# module.net
KiCad netlist of a schematic drawn in EAGLE
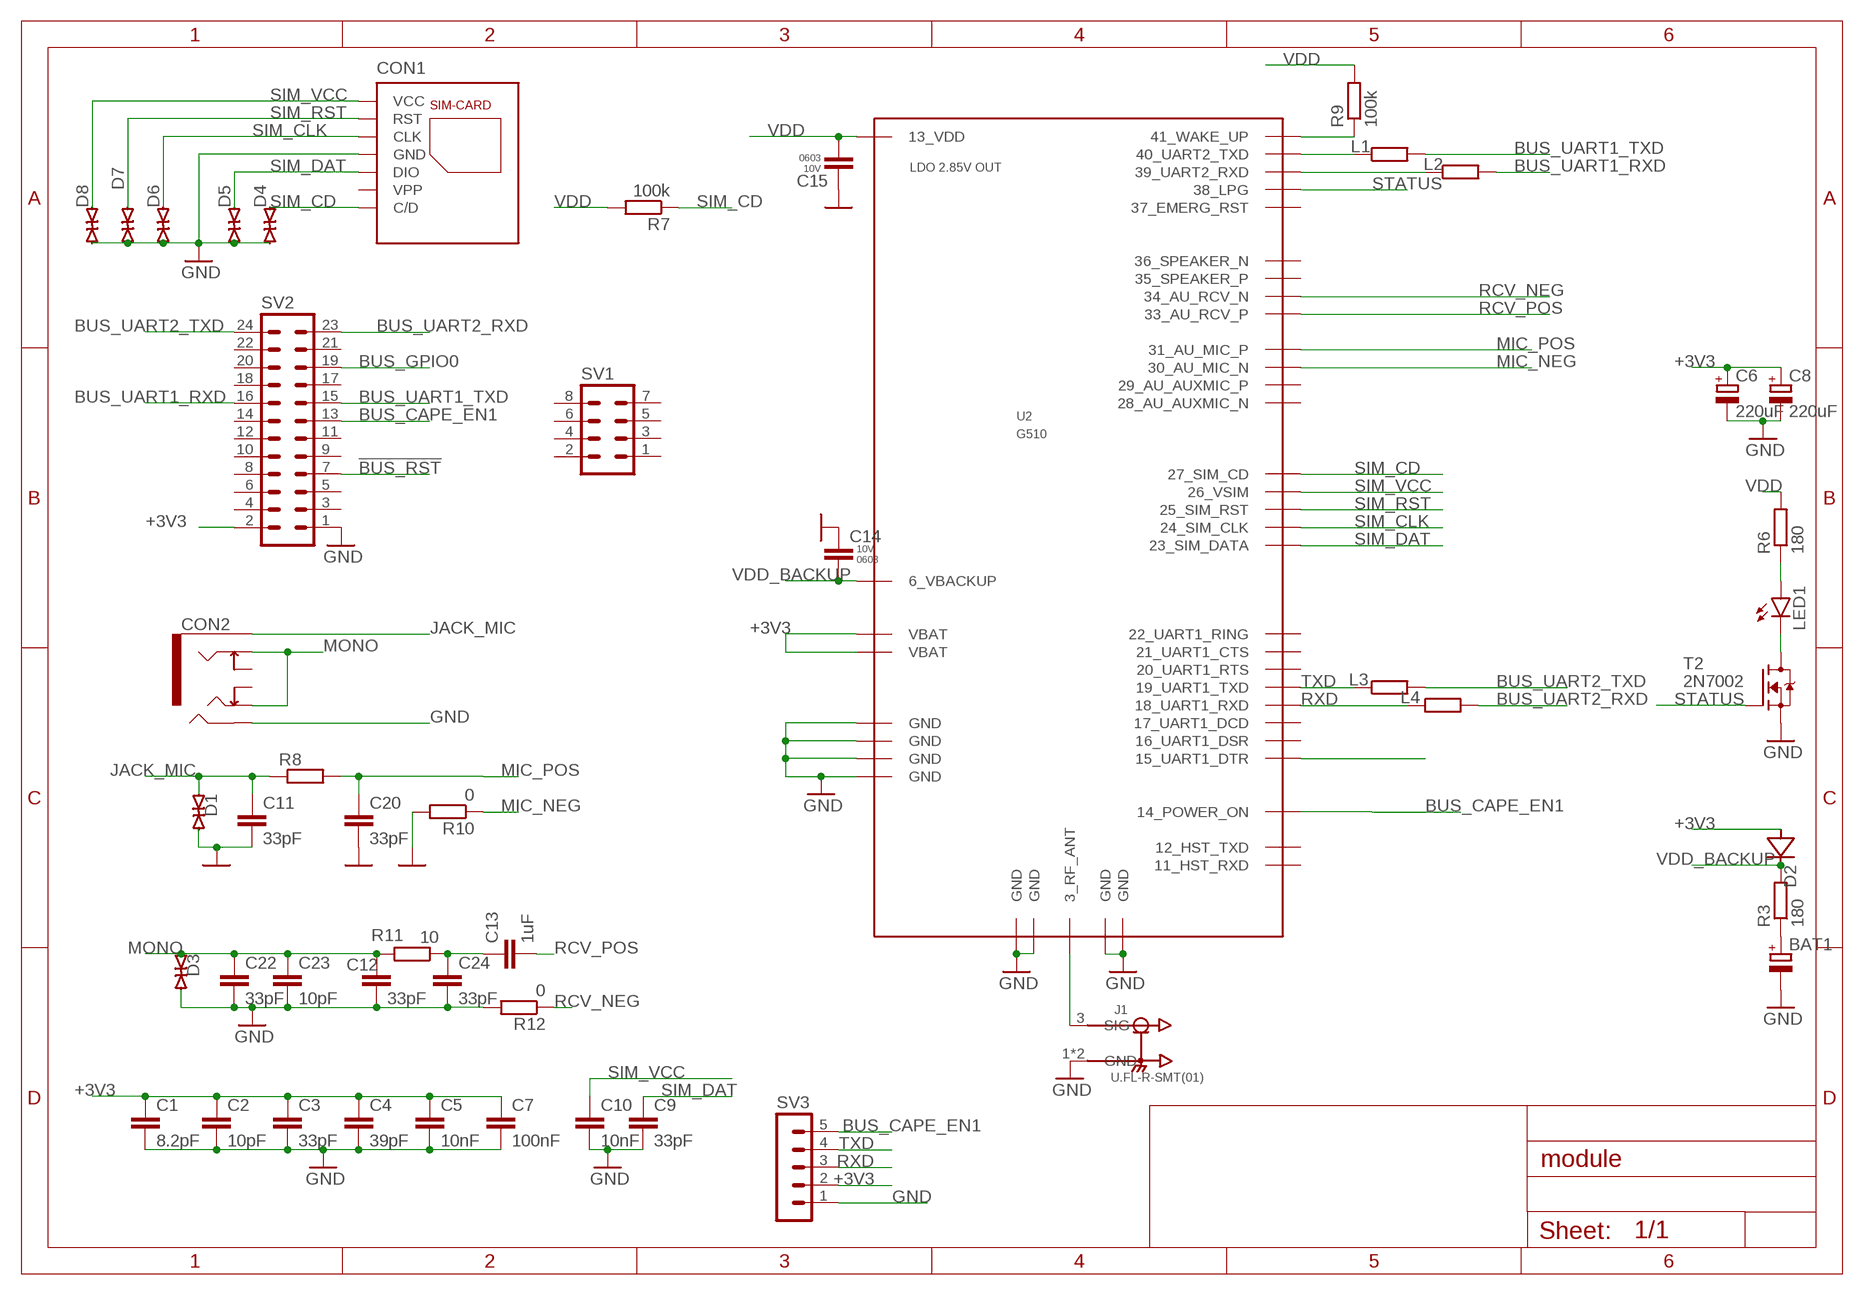
[diagram p0: schematic, sheet 1]

(export (version "E")
  (design (tool "Eeschema 10.0.6"))
  (components
    (comp (ref "BAT1")
      (value "DCK-3R3E224U-E")
      (footprint "eagle-import:621")
      (libsource (lib "eagle-import") (part "DCK-3R3E224U-E"))
    )
    (comp (ref "C1")
      (value "8.2pF")
      (footprint "eagle-import:C0402K")
      (libsource (lib "eagle-import") (part "CAP-0402"))
    )
    (comp (ref "C2")
      (value "10pF")
      (footprint "eagle-import:C0402K")
      (libsource (lib "eagle-import") (part "CAP-0402"))
    )
    (comp (ref "C3")
      (value "33pF")
      (footprint "eagle-import:C0402K")
      (libsource (lib "eagle-import") (part "CAP-0402"))
    )
    (comp (ref "C4")
      (value "39pF")
      (footprint "eagle-import:C0402K")
      (libsource (lib "eagle-import") (part "CAP-0402"))
    )
    (comp (ref "C5")
      (value "10nF")
      (footprint "eagle-import:C0603")
      (libsource (lib "eagle-import") (part "C-EUC0603"))
    )
    (comp (ref "C6")
      (value "220uF")
      (footprint "eagle-import:SMC_C")
      (libsource (lib "eagle-import") (part "CAP-POL-SMC"))
    )
    (comp (ref "C7")
      (value "100nF")
      (footprint "eagle-import:C0603")
      (libsource (lib "eagle-import") (part "C-EUC0603"))
    )
    (comp (ref "C8")
      (value "220uF")
      (footprint "eagle-import:SMC_C")
      (libsource (lib "eagle-import") (part "CAP-POL-SMC"))
    )
    (comp (ref "C9")
      (value "33pF")
      (footprint "eagle-import:C0603")
      (libsource (lib "eagle-import") (part "CAP-0603"))
    )
    (comp (ref "C10")
      (value "10nF")
      (footprint "eagle-import:C0603")
      (libsource (lib "eagle-import") (part "CAP-0603"))
    )
    (comp (ref "C11")
      (value "33pF")
      (footprint "eagle-import:C0402K")
      (libsource (lib "eagle-import") (part "CAP-0402"))
    )
    (comp (ref "C12")
      (value "33pF")
      (footprint "eagle-import:C0402K")
      (libsource (lib "eagle-import") (part "CAP-0402"))
    )
    (comp (ref "C13")
      (value "1uF")
      (footprint "eagle-import:C0402K")
      (libsource (lib "eagle-import") (part "CAP-0402"))
    )
    (comp (ref "C14")
      (value "CAP-0603")
      (footprint "eagle-import:C0603")
      (fields (field (name "RATING") "10V") (field (name "PACKAGE") "0603"))
      (libsource (lib "eagle-import") (part "CAP-0603"))
    )
    (comp (ref "C15")
      (value "CAP-0603")
      (footprint "eagle-import:C0603")
      (fields (field (name "RATING") "10V") (field (name "PACKAGE") "0603"))
      (libsource (lib "eagle-import") (part "CAP-0603"))
    )
    (comp (ref "C20")
      (value "33pF")
      (footprint "eagle-import:C0402K")
      (libsource (lib "eagle-import") (part "CAP-0402"))
    )
    (comp (ref "C22")
      (value "33pF")
      (footprint "eagle-import:C0402K")
      (libsource (lib "eagle-import") (part "CAP-0402"))
    )
    (comp (ref "C23")
      (value "10pF")
      (footprint "eagle-import:C0402K")
      (libsource (lib "eagle-import") (part "CAP-0402"))
    )
    (comp (ref "C24")
      (value "33pF")
      (footprint "eagle-import:C0402K")
      (libsource (lib "eagle-import") (part "CAP-0402"))
    )
    (comp (ref "CON1")
      (value "115Q-BCA0")
      (footprint "eagle-import:115Q")
      (libsource (lib "eagle-import") (part "115Q-BCA0"))
    )
    (comp (ref "CON2")
      (value "1503-21")
      (footprint "eagle-import:150321")
      (libsource (lib "eagle-import") (part "1503-21"))
    )
    (comp (ref "D1")
      (value "ESD9B5.0ST5G")
      (footprint "eagle-import:SOD1006X40")
      (libsource (lib "eagle-import") (part "ESD9B5.0ST5G"))
    )
    (comp (ref "D2")
      (value "1N4148WS")
      (footprint "eagle-import:SOD323")
      (libsource (lib "eagle-import") (part "1N4148WS"))
    )
    (comp (ref "D3")
      (value "ESD9B5.0ST5G")
      (footprint "eagle-import:SOD1006X40")
      (libsource (lib "eagle-import") (part "ESD9B5.0ST5G"))
    )
    (comp (ref "D4")
      (value "ESD9B5.0ST5G")
      (footprint "eagle-import:SOD1006X40")
      (libsource (lib "eagle-import") (part "ESD9B5.0ST5G"))
    )
    (comp (ref "D5")
      (value "ESD9B5.0ST5G")
      (footprint "eagle-import:SOD1006X40")
      (libsource (lib "eagle-import") (part "ESD9B5.0ST5G"))
    )
    (comp (ref "D6")
      (value "ESD9B5.0ST5G")
      (footprint "eagle-import:SOD1006X40")
      (libsource (lib "eagle-import") (part "ESD9B5.0ST5G"))
    )
    (comp (ref "D7")
      (value "ESD9B5.0ST5G")
      (footprint "eagle-import:SOD1006X40")
      (libsource (lib "eagle-import") (part "ESD9B5.0ST5G"))
    )
    (comp (ref "D8")
      (value "ESD9B5.0ST5G")
      (footprint "eagle-import:SOD1006X40")
      (libsource (lib "eagle-import") (part "ESD9B5.0ST5G"))
    )
    (comp (ref "J1")
      (value "U.FL-R-SMT(01)")
      (footprint "eagle-import:HRS_U.FL-R-SMT(01)")
      (fields (field (name "MF") "Hirose") (field (name "MP") "U.FL-R-SMT_01_"))
      (libsource (lib "eagle-import") (part "U.FL-R-SMT(01)"))
    )
    (comp (ref "L1")
      (value "RES-0603")
      (footprint "eagle-import:R0603")
      (libsource (lib "eagle-import") (part "RES-0603"))
    )
    (comp (ref "L2")
      (value "RES-0603")
      (footprint "eagle-import:R0603")
      (libsource (lib "eagle-import") (part "RES-0603"))
    )
    (comp (ref "L3")
      (value "RES-0603")
      (footprint "eagle-import:R0603")
      (libsource (lib "eagle-import") (part "RES-0603"))
    )
    (comp (ref "L4")
      (value "RES-0603")
      (footprint "eagle-import:R0603")
      (libsource (lib "eagle-import") (part "RES-0603"))
    )
    (comp (ref "LED1")
      (value "LEDCHIP-LED0603")
      (footprint "eagle-import:CHIP-LED0603")
      (libsource (lib "eagle-import") (part "LEDCHIP-LED0603"))
    )
    (comp (ref "R3")
      (value "180")
      (footprint "eagle-import:R0603")
      (libsource (lib "eagle-import") (part "RES-0603"))
    )
    (comp (ref "R6")
      (value "180")
      (footprint "eagle-import:R0603")
      (libsource (lib "eagle-import") (part "RES-0603"))
    )
    (comp (ref "R7")
      (value "100k")
      (footprint "eagle-import:R0603")
      (libsource (lib "eagle-import") (part "RES-0603"))
    )
    (comp (ref "R8")
      (value "R-EU_R0402")
      (footprint "eagle-import:R0402")
      (libsource (lib "eagle-import") (part "R-EU_R0402"))
    )
    (comp (ref "R9")
      (value "100k")
      (footprint "eagle-import:R0603")
      (libsource (lib "eagle-import") (part "RES-0603"))
    )
    (comp (ref "R10")
      (value "0")
      (footprint "eagle-import:R0402")
      (libsource (lib "eagle-import") (part "R-EU_R0402"))
    )
    (comp (ref "R11")
      (value "10")
      (footprint "eagle-import:R0402")
      (libsource (lib "eagle-import") (part "R-EU_R0402"))
    )
    (comp (ref "R12")
      (value "0")
      (footprint "eagle-import:R0402")
      (libsource (lib "eagle-import") (part "R-EU_R0402"))
    )
    (comp (ref "SV1")
      (value "MA04-2")
      (footprint "eagle-import:MA04-2")
      (libsource (lib "eagle-import") (part "MA04-2"))
    )
    (comp (ref "SV2")
      (value "MA12-2")
      (footprint "eagle-import:MA12-2")
      (libsource (lib "eagle-import") (part "MA12-2"))
    )
    (comp (ref "SV3")
      (value "MA05-1")
      (footprint "eagle-import:MA05-1")
      (libsource (lib "eagle-import") (part "MA05-1"))
    )
    (comp (ref "T2")
      (value "2N7002")
      (footprint "eagle-import:SOT95P240X110-3")
      (libsource (lib "eagle-import") (part "2N7002"))
    )
    (comp (ref "U2")
      (value "G510")
      (footprint "eagle-import:G510")
      (libsource (lib "eagle-import") (part "G510"))
    )
  )
  (nets
    (net (code "1") (name "/+3V3") (class "Default")
      (node (ref "C1") (pin "1") (pinfunction "1_1") (pintype "passive"))
      (node (ref "C2") (pin "1") (pinfunction "1_1") (pintype "passive"))
      (node (ref "C3") (pin "1") (pinfunction "1_1") (pintype "passive"))
      (node (ref "C4") (pin "1") (pinfunction "1_1") (pintype "passive"))
      (node (ref "C5") (pin "1") (pinfunction "1_1") (pintype "passive"))
      (node (ref "C6") (pin "+") (pinfunction "+_+") (pintype "passive"))
      (node (ref "C7") (pin "1") (pinfunction "1_1") (pintype "passive"))
      (node (ref "C8") (pin "+") (pinfunction "+_+") (pintype "passive"))
      (node (ref "D2") (pin "A") (pinfunction "A_A") (pintype "passive"))
      (node (ref "SV2") (pin "2") (pinfunction "2_2") (pintype "passive"))
      (node (ref "SV3") (pin "2") (pinfunction "2_2") (pintype "passive"))
      (node (ref "U2") (pin "10_VBAT") (pinfunction "VBAT_10_VBAT") (pintype "power_in"))
      (node (ref "U2") (pin "9_VBAT") (pinfunction "VBAT_9_VBAT") (pintype "power_in"))
    )
    (net (code "2") (name "/BUS_CAPE_EN1") (class "Default")
      (node (ref "SV2") (pin "13") (pinfunction "13_13") (pintype "passive"))
      (node (ref "SV3") (pin "5") (pinfunction "5_5") (pintype "passive"))
      (node (ref "U2") (pin "14_POWER_ON") (pinfunction "14_POWER_ON_14_POWER_ON") (pintype "input"))
    )
    (net (code "3") (name "/BUS_GPIO0") (class "Default")
      (node (ref "SV2") (pin "19") (pinfunction "19_19") (pintype "passive"))
    )
    (net (code "4") (name "/BUS_UART1_RXD") (class "Default")
      (node (ref "L2") (pin "2") (pinfunction "2_2") (pintype "passive"))
      (node (ref "SV2") (pin "16") (pinfunction "16_16") (pintype "passive"))
    )
    (net (code "5") (name "/BUS_UART1_TXD") (class "Default")
      (node (ref "L1") (pin "2") (pinfunction "2_2") (pintype "passive"))
      (node (ref "SV2") (pin "15") (pinfunction "15_15") (pintype "passive"))
    )
    (net (code "6") (name "/BUS_UART2_RXD") (class "Default")
      (node (ref "L4") (pin "2") (pinfunction "2_2") (pintype "passive"))
      (node (ref "SV2") (pin "23") (pinfunction "23_23") (pintype "passive"))
    )
    (net (code "7") (name "/BUS_UART2_TXD") (class "Default")
      (node (ref "L3") (pin "2") (pinfunction "2_2") (pintype "passive"))
      (node (ref "SV2") (pin "24") (pinfunction "24_24") (pintype "passive"))
    )
    (net (code "8") (name "/JACK_MIC") (class "Default")
      (node (ref "C11") (pin "1") (pinfunction "1_1") (pintype "passive"))
      (node (ref "CON2") (pin "1") (pinfunction "1_1") (pintype "bidirectional"))
      (node (ref "D1") (pin "1") (pinfunction "A_1") (pintype "passive"))
      (node (ref "R8") (pin "1") (pinfunction "1_1") (pintype "passive"))
    )
    (net (code "9") (name "/MIC_NEG") (class "Default")
      (node (ref "R10") (pin "1") (pinfunction "1_1") (pintype "passive"))
      (node (ref "U2") (pin "30_AU_MIC_N") (pinfunction "30_AU_MIC_N_30_AU_MIC_N") (pintype "bidirectional"))
    )
    (net (code "10") (name "/MIC_POS") (class "Default")
      (node (ref "C20") (pin "1") (pinfunction "1_1") (pintype "passive"))
      (node (ref "R8") (pin "2") (pinfunction "2_2") (pintype "passive"))
      (node (ref "U2") (pin "31_AU_MIC_P") (pinfunction "31_AU_MIC_P_31_AU_MIC_P") (pintype "bidirectional"))
    )
    (net (code "11") (name "/MONO") (class "Default")
      (node (ref "C12") (pin "1") (pinfunction "1_1") (pintype "passive"))
      (node (ref "C22") (pin "1") (pinfunction "1_1") (pintype "passive"))
      (node (ref "C23") (pin "1") (pinfunction "1_1") (pintype "passive"))
      (node (ref "CON2") (pin "3") (pinfunction "3_3") (pintype "bidirectional"))
      (node (ref "CON2") (pin "5") (pinfunction "5_5") (pintype "bidirectional"))
      (node (ref "D3") (pin "1") (pinfunction "A_1") (pintype "passive"))
      (node (ref "R11") (pin "2") (pinfunction "2_2") (pintype "passive"))
    )
    (net (code "12") (name "/RCV_NEG") (class "Default")
      (node (ref "R12") (pin "1") (pinfunction "1_1") (pintype "passive"))
      (node (ref "U2") (pin "34_AU_RCV_N") (pinfunction "34_AU_RCV_N_34_AU_RCV_N") (pintype "bidirectional"))
    )
    (net (code "13") (name "/RCV_POS") (class "Default")
      (node (ref "C13") (pin "2") (pinfunction "2_2") (pintype "passive"))
      (node (ref "U2") (pin "33_AU_RCV_P") (pinfunction "33_AU_RCV_P_33_AU_RCV_P") (pintype "bidirectional"))
    )
    (net (code "14") (name "/RXD") (class "Default")
      (node (ref "L4") (pin "1") (pinfunction "1_1") (pintype "passive"))
      (node (ref "SV3") (pin "3") (pinfunction "3_3") (pintype "passive"))
      (node (ref "U2") (pin "18_UART1_RXD") (pinfunction "18_UART1_RXD_18_UART1_RXD") (pintype "input"))
    )
    (net (code "15") (name "/SIM_CD") (class "Default")
      (node (ref "CON1") (pin "CD") (pinfunction "C/D_CD") (pintype "passive"))
      (node (ref "D4") (pin "2") (pinfunction "C_2") (pintype "passive"))
      (node (ref "R7") (pin "1") (pinfunction "1_1") (pintype "passive"))
      (node (ref "U2") (pin "27_SIM_CD") (pinfunction "27_SIM_CD_27_SIM_CD") (pintype "bidirectional"))
    )
    (net (code "16") (name "/SIM_CLK") (class "Default")
      (node (ref "CON1") (pin "P3") (pinfunction "CLK_P3") (pintype "passive"))
      (node (ref "D6") (pin "2") (pinfunction "C_2") (pintype "passive"))
      (node (ref "U2") (pin "24_SIM_CLK") (pinfunction "24_SIM_CLK_24_SIM_CLK") (pintype "bidirectional"))
    )
    (net (code "17") (name "/SIM_DAT") (class "Default")
      (node (ref "C9") (pin "1") (pinfunction "1_1") (pintype "passive"))
      (node (ref "CON1") (pin "P7") (pinfunction "DIO_P7") (pintype "passive"))
      (node (ref "D5") (pin "2") (pinfunction "C_2") (pintype "passive"))
      (node (ref "U2") (pin "23_SIM_DATA") (pinfunction "23_SIM_DATA_23_SIM_DATA") (pintype "bidirectional"))
    )
    (net (code "18") (name "/SIM_RST") (class "Default")
      (node (ref "CON1") (pin "P2") (pinfunction "RST_P2") (pintype "passive"))
      (node (ref "D7") (pin "2") (pinfunction "C_2") (pintype "passive"))
      (node (ref "U2") (pin "25_SIM_RST") (pinfunction "25_SIM_RST_25_SIM_RST") (pintype "bidirectional"))
    )
    (net (code "19") (name "/SIM_VCC") (class "Default")
      (node (ref "C10") (pin "1") (pinfunction "1_1") (pintype "passive"))
      (node (ref "CON1") (pin "P1") (pinfunction "VCC_P1") (pintype "passive"))
      (node (ref "D8") (pin "2") (pinfunction "C_2") (pintype "passive"))
      (node (ref "U2") (pin "26_VSIM") (pinfunction "26_VSIM_26_VSIM") (pintype "bidirectional"))
    )
    (net (code "20") (name "/STATUS") (class "Default")
      (node (ref "T2") (pin "1") (pinfunction "G_1") (pintype "passive"))
      (node (ref "U2") (pin "38_LPG") (pinfunction "38_LPG_38_LPG") (pintype "output"))
    )
    (net (code "21") (name "/TXD") (class "Default")
      (node (ref "L3") (pin "1") (pinfunction "1_1") (pintype "passive"))
      (node (ref "SV3") (pin "4") (pinfunction "4_4") (pintype "passive"))
      (node (ref "U2") (pin "19_UART1_TXD") (pinfunction "19_UART1_TXD_19_UART1_TXD") (pintype "output"))
    )
    (net (code "22") (name "/VDD") (class "Default")
      (node (ref "C15") (pin "2") (pinfunction "2_2") (pintype "passive"))
      (node (ref "R6") (pin "2") (pinfunction "2_2") (pintype "passive"))
      (node (ref "R7") (pin "2") (pinfunction "2_2") (pintype "passive"))
      (node (ref "R9") (pin "2") (pinfunction "2_2") (pintype "passive"))
      (node (ref "U2") (pin "13_VDD") (pinfunction "13_VDD_13_VDD") (pintype "power_in"))
    )
    (net (code "23") (name "/VDD_BACKUP") (class "Default")
      (node (ref "C14") (pin "2") (pinfunction "2_2") (pintype "passive"))
      (node (ref "D2") (pin "K") (pinfunction "C_K") (pintype "passive"))
      (node (ref "R3") (pin "2") (pinfunction "2_2") (pintype "passive"))
      (node (ref "U2") (pin "6_VBACKUP") (pinfunction "6_VBACKUP_6_VBACKUP") (pintype "power_in"))
    )
    (net (code "24") (name "/~{BUS_RST}") (class "Default")
      (node (ref "SV2") (pin "7") (pinfunction "7_7") (pintype "passive"))
    )
    (net (code "25") (name "GND") (class "Default")
      (node (ref "BAT1") (pin "-") (pinfunction "-_-") (pintype "passive"))
      (node (ref "C1") (pin "2") (pinfunction "2_2") (pintype "passive"))
      (node (ref "C10") (pin "2") (pinfunction "2_2") (pintype "passive"))
      (node (ref "C11") (pin "2") (pinfunction "2_2") (pintype "passive"))
      (node (ref "C12") (pin "2") (pinfunction "2_2") (pintype "passive"))
      (node (ref "C14") (pin "1") (pinfunction "1_1") (pintype "passive"))
      (node (ref "C15") (pin "1") (pinfunction "1_1") (pintype "passive"))
      (node (ref "C2") (pin "2") (pinfunction "2_2") (pintype "passive"))
      (node (ref "C20") (pin "2") (pinfunction "2_2") (pintype "passive"))
      (node (ref "C22") (pin "2") (pinfunction "2_2") (pintype "passive"))
      (node (ref "C23") (pin "2") (pinfunction "2_2") (pintype "passive"))
      (node (ref "C24") (pin "2") (pinfunction "2_2") (pintype "passive"))
      (node (ref "C3") (pin "2") (pinfunction "2_2") (pintype "passive"))
      (node (ref "C4") (pin "2") (pinfunction "2_2") (pintype "passive"))
      (node (ref "C5") (pin "2") (pinfunction "2_2") (pintype "passive"))
      (node (ref "C6") (pin "-") (pinfunction "-_-") (pintype "passive"))
      (node (ref "C7") (pin "2") (pinfunction "2_2") (pintype "passive"))
      (node (ref "C8") (pin "-") (pinfunction "-_-") (pintype "passive"))
      (node (ref "C9") (pin "2") (pinfunction "2_2") (pintype "passive"))
      (node (ref "CON1") (pin "GND1") (pinfunction "GND_GND1") (pintype "passive"))
      (node (ref "CON1") (pin "GND2") (pinfunction "GND_GND2") (pintype "passive"))
      (node (ref "CON1") (pin "GND3") (pinfunction "GND_GND3") (pintype "passive"))
      (node (ref "CON1") (pin "GND4") (pinfunction "GND_GND4") (pintype "passive"))
      (node (ref "CON1") (pin "P5") (pinfunction "GND_P5") (pintype "passive"))
      (node (ref "CON2") (pin "2") (pinfunction "2_2") (pintype "bidirectional"))
      (node (ref "D1") (pin "2") (pinfunction "C_2") (pintype "passive"))
      (node (ref "D3") (pin "2") (pinfunction "C_2") (pintype "passive"))
      (node (ref "D4") (pin "1") (pinfunction "A_1") (pintype "passive"))
      (node (ref "D5") (pin "1") (pinfunction "A_1") (pintype "passive"))
      (node (ref "D6") (pin "1") (pinfunction "A_1") (pintype "passive"))
      (node (ref "D7") (pin "1") (pinfunction "A_1") (pintype "passive"))
      (node (ref "D8") (pin "1") (pinfunction "A_1") (pintype "passive"))
      (node (ref "J1") (pin "1") (pinfunction "GND_1") (pintype "passive"))
      (node (ref "J1") (pin "2") (pinfunction "GND_2") (pintype "passive"))
      (node (ref "R10") (pin "2") (pinfunction "2_2") (pintype "passive"))
      (node (ref "R12") (pin "2") (pinfunction "2_2") (pintype "passive"))
      (node (ref "SV2") (pin "1") (pinfunction "1_1") (pintype "passive"))
      (node (ref "SV3") (pin "1") (pinfunction "1_1") (pintype "passive"))
      (node (ref "T2") (pin "2") (pinfunction "S_2") (pintype "passive"))
      (node (ref "U2") (pin "1_GND") (pinfunction "GND_1_GND") (pintype "power_in"))
      (node (ref "U2") (pin "2_GND") (pinfunction "GND_2_GND") (pintype "power_in"))
      (node (ref "U2") (pin "32_GND") (pinfunction "GND_32_GND") (pintype "power_in"))
      (node (ref "U2") (pin "42_GND") (pinfunction "GND_42_GND") (pintype "power_in"))
      (node (ref "U2") (pin "4_GND") (pinfunction "GND_4_GND") (pintype "power_in"))
      (node (ref "U2") (pin "5_GND") (pinfunction "GND_5_GND") (pintype "power_in"))
      (node (ref "U2") (pin "7_GND") (pinfunction "GND_7_GND") (pintype "power_in"))
      (node (ref "U2") (pin "8_GND") (pinfunction "GND_8_GND") (pintype "power_in"))
    )
    (net (code "26") (name "Net-(BAT1-Pad+)") (class "Default")
      (node (ref "BAT1") (pin "+") (pinfunction "+_+") (pintype "passive"))
      (node (ref "R3") (pin "1") (pinfunction "1_1") (pintype "passive"))
    )
    (net (code "27") (name "Net-(C13-Pad1)") (class "Default")
      (node (ref "C13") (pin "1") (pinfunction "1_1") (pintype "passive"))
      (node (ref "C24") (pin "1") (pinfunction "1_1") (pintype "passive"))
      (node (ref "R11") (pin "1") (pinfunction "1_1") (pintype "passive"))
    )
    (net (code "28") (name "Net-(J1-SIG)") (class "Default")
      (node (ref "J1") (pin "3") (pinfunction "SIG_3") (pintype "passive"))
      (node (ref "U2") (pin "3_RF_ANT") (pinfunction "3_RF_ANT_3_RF_ANT") (pintype "bidirectional"))
    )
    (net (code "29") (name "Net-(L1-Pad1)") (class "Default")
      (node (ref "L1") (pin "1") (pinfunction "1_1") (pintype "passive"))
      (node (ref "U2") (pin "40_UART2_TXD") (pinfunction "40_UART2_TXD_40_UART2_TXD") (pintype "output"))
    )
    (net (code "30") (name "Net-(L2-Pad1)") (class "Default")
      (node (ref "L2") (pin "1") (pinfunction "1_1") (pintype "passive"))
      (node (ref "U2") (pin "39_UART2_RXD") (pinfunction "39_UART2_RXD_39_UART2_RXD") (pintype "input"))
    )
    (net (code "31") (name "Net-(LED1-PadA)") (class "Default")
      (node (ref "LED1") (pin "A") (pinfunction "A_A") (pintype "passive"))
      (node (ref "R6") (pin "1") (pinfunction "1_1") (pintype "passive"))
    )
    (net (code "32") (name "Net-(R9-Pad1)") (class "Default")
      (node (ref "R9") (pin "1") (pinfunction "1_1") (pintype "passive"))
      (node (ref "U2") (pin "41_WAKE_UP") (pinfunction "41_WAKE_UP_41_WAKE_UP") (pintype "bidirectional"))
    )
    (net (code "33") (name "Net-(T2-D)") (class "Default")
      (node (ref "LED1") (pin "C") (pinfunction "C_C") (pintype "passive"))
      (node (ref "T2") (pin "3") (pinfunction "D_3") (pintype "passive"))
    )
    (net (code "34") (name "unconnected-(CON1-VPP-PadP6)") (class "Default")
      (node (ref "CON1") (pin "P6") (pinfunction "VPP_P6") (pintype "passive"))
    )
    (net (code "35") (name "unconnected-(CON2-Pad4)") (class "Default")
      (node (ref "CON2") (pin "4") (pinfunction "4_4") (pintype "bidirectional"))
    )
    (net (code "36") (name "unconnected-(CON2-Pad6)") (class "Default")
      (node (ref "CON2") (pin "6") (pinfunction "6_6") (pintype "bidirectional"))
    )
    (net (code "37") (name "unconnected-(SV1-Pad1)") (class "Default")
      (node (ref "SV1") (pin "1") (pinfunction "1_1") (pintype "passive"))
    )
    (net (code "38") (name "unconnected-(SV1-Pad2)") (class "Default")
      (node (ref "SV1") (pin "2") (pinfunction "2_2") (pintype "passive"))
    )
    (net (code "39") (name "unconnected-(SV1-Pad3)") (class "Default")
      (node (ref "SV1") (pin "3") (pinfunction "3_3") (pintype "passive"))
    )
    (net (code "40") (name "unconnected-(SV1-Pad4)") (class "Default")
      (node (ref "SV1") (pin "4") (pinfunction "4_4") (pintype "passive"))
    )
    (net (code "41") (name "unconnected-(SV1-Pad5)") (class "Default")
      (node (ref "SV1") (pin "5") (pinfunction "5_5") (pintype "passive"))
    )
    (net (code "42") (name "unconnected-(SV1-Pad6)") (class "Default")
      (node (ref "SV1") (pin "6") (pinfunction "6_6") (pintype "passive"))
    )
    (net (code "43") (name "unconnected-(SV1-Pad7)") (class "Default")
      (node (ref "SV1") (pin "7") (pinfunction "7_7") (pintype "passive"))
    )
    (net (code "44") (name "unconnected-(SV1-Pad8)") (class "Default")
      (node (ref "SV1") (pin "8") (pinfunction "8_8") (pintype "passive"))
    )
    (net (code "45") (name "unconnected-(SV2-Pad3)") (class "Default")
      (node (ref "SV2") (pin "3") (pinfunction "3_3") (pintype "passive"))
    )
    (net (code "46") (name "unconnected-(SV2-Pad4)") (class "Default")
      (node (ref "SV2") (pin "4") (pinfunction "4_4") (pintype "passive"))
    )
    (net (code "47") (name "unconnected-(SV2-Pad5)") (class "Default")
      (node (ref "SV2") (pin "5") (pinfunction "5_5") (pintype "passive"))
    )
    (net (code "48") (name "unconnected-(SV2-Pad6)") (class "Default")
      (node (ref "SV2") (pin "6") (pinfunction "6_6") (pintype "passive"))
    )
    (net (code "49") (name "unconnected-(SV2-Pad8)") (class "Default")
      (node (ref "SV2") (pin "8") (pinfunction "8_8") (pintype "passive"))
    )
    (net (code "50") (name "unconnected-(SV2-Pad9)") (class "Default")
      (node (ref "SV2") (pin "9") (pinfunction "9_9") (pintype "passive"))
    )
    (net (code "51") (name "unconnected-(SV2-Pad10)") (class "Default")
      (node (ref "SV2") (pin "10") (pinfunction "10_10") (pintype "passive"))
    )
    (net (code "52") (name "unconnected-(SV2-Pad11)") (class "Default")
      (node (ref "SV2") (pin "11") (pinfunction "11_11") (pintype "passive"))
    )
    (net (code "53") (name "unconnected-(SV2-Pad12)") (class "Default")
      (node (ref "SV2") (pin "12") (pinfunction "12_12") (pintype "passive"))
    )
    (net (code "54") (name "unconnected-(SV2-Pad14)") (class "Default")
      (node (ref "SV2") (pin "14") (pinfunction "14_14") (pintype "passive"))
    )
    (net (code "55") (name "unconnected-(SV2-Pad17)") (class "Default")
      (node (ref "SV2") (pin "17") (pinfunction "17_17") (pintype "passive"))
    )
    (net (code "56") (name "unconnected-(SV2-Pad18)") (class "Default")
      (node (ref "SV2") (pin "18") (pinfunction "18_18") (pintype "passive"))
    )
    (net (code "57") (name "unconnected-(SV2-Pad20)") (class "Default")
      (node (ref "SV2") (pin "20") (pinfunction "20_20") (pintype "passive"))
    )
    (net (code "58") (name "unconnected-(SV2-Pad21)") (class "Default")
      (node (ref "SV2") (pin "21") (pinfunction "21_21") (pintype "passive"))
    )
    (net (code "59") (name "unconnected-(SV2-Pad22)") (class "Default")
      (node (ref "SV2") (pin "22") (pinfunction "22_22") (pintype "passive"))
    )
    (net (code "60") (name "unconnected-(U2-11_HST_RXD-Pad11_HSTRXD)") (class "Default")
      (node (ref "U2") (pin "11_HSTRXD") (pinfunction "11_HST_RXD_11_HSTRXD") (pintype "input"))
    )
    (net (code "61") (name "unconnected-(U2-Pad12_HST_TXD)") (class "Default")
      (node (ref "U2") (pin "12_HST_TXD") (pinfunction "12_HST_TXD_12_HST_TXD") (pintype "output"))
    )
    (net (code "62") (name "unconnected-(U2-Pad15_UART1_DTR)") (class "Default")
      (node (ref "U2") (pin "15_UART1_DTR") (pinfunction "15_UART1_DTR_15_UART1_DTR") (pintype "bidirectional"))
    )
    (net (code "63") (name "unconnected-(U2-Pad16_UART1_DSR)") (class "Default")
      (node (ref "U2") (pin "16_UART1_DSR") (pinfunction "16_UART1_DSR_16_UART1_DSR") (pintype "bidirectional"))
    )
    (net (code "64") (name "unconnected-(U2-Pad17_UART1_DCD)") (class "Default")
      (node (ref "U2") (pin "17_UART1_DCD") (pinfunction "17_UART1_DCD_17_UART1_DCD") (pintype "bidirectional"))
    )
    (net (code "65") (name "unconnected-(U2-Pad20_UART1_RTS)") (class "Default")
      (node (ref "U2") (pin "20_UART1_RTS") (pinfunction "20_UART1_RTS_20_UART1_RTS") (pintype "bidirectional"))
    )
    (net (code "66") (name "unconnected-(U2-Pad21_UART1_CTS)") (class "Default")
      (node (ref "U2") (pin "21_UART1_CTS") (pinfunction "21_UART1_CTS_21_UART1_CTS") (pintype "bidirectional"))
    )
    (net (code "67") (name "unconnected-(U2-Pad22_UART1_RING)") (class "Default")
      (node (ref "U2") (pin "22_UART1_RING") (pinfunction "22_UART1_RING_22_UART1_RING") (pintype "bidirectional"))
    )
    (net (code "68") (name "unconnected-(U2-Pad28_AU_AUXMIC_N)") (class "Default")
      (node (ref "U2") (pin "28_AU_AUXMIC_N") (pinfunction "28_AU_AUXMIC_N_28_AU_AUXMIC_N") (pintype "bidirectional"))
    )
    (net (code "69") (name "unconnected-(U2-Pad29_AU_AUXMIC_P)") (class "Default")
      (node (ref "U2") (pin "29_AU_AUXMIC_P") (pinfunction "29_AU_AUXMIC_P_29_AU_AUXMIC_P") (pintype "bidirectional"))
    )
    (net (code "70") (name "unconnected-(U2-Pad35_SPEAKER_P)") (class "Default")
      (node (ref "U2") (pin "35_SPEAKER_P") (pinfunction "35_SPEAKER_P_35_SPEAKER_P") (pintype "bidirectional"))
    )
    (net (code "71") (name "unconnected-(U2-Pad36_SPEAKER_N)") (class "Default")
      (node (ref "U2") (pin "36_SPEAKER_N") (pinfunction "36_SPEAKER_N_36_SPEAKER_N") (pintype "bidirectional"))
    )
    (net (code "72") (name "unconnected-(U2-Pad37_EMERG_RST)") (class "Default")
      (node (ref "U2") (pin "37_EMERG_RST") (pinfunction "37_EMERG_RST_37_EMERG_RST") (pintype "input"))
    )
  )
)
